# Negative_Rail.net
KiCad netlist of a schematic drawn in Altium Designer
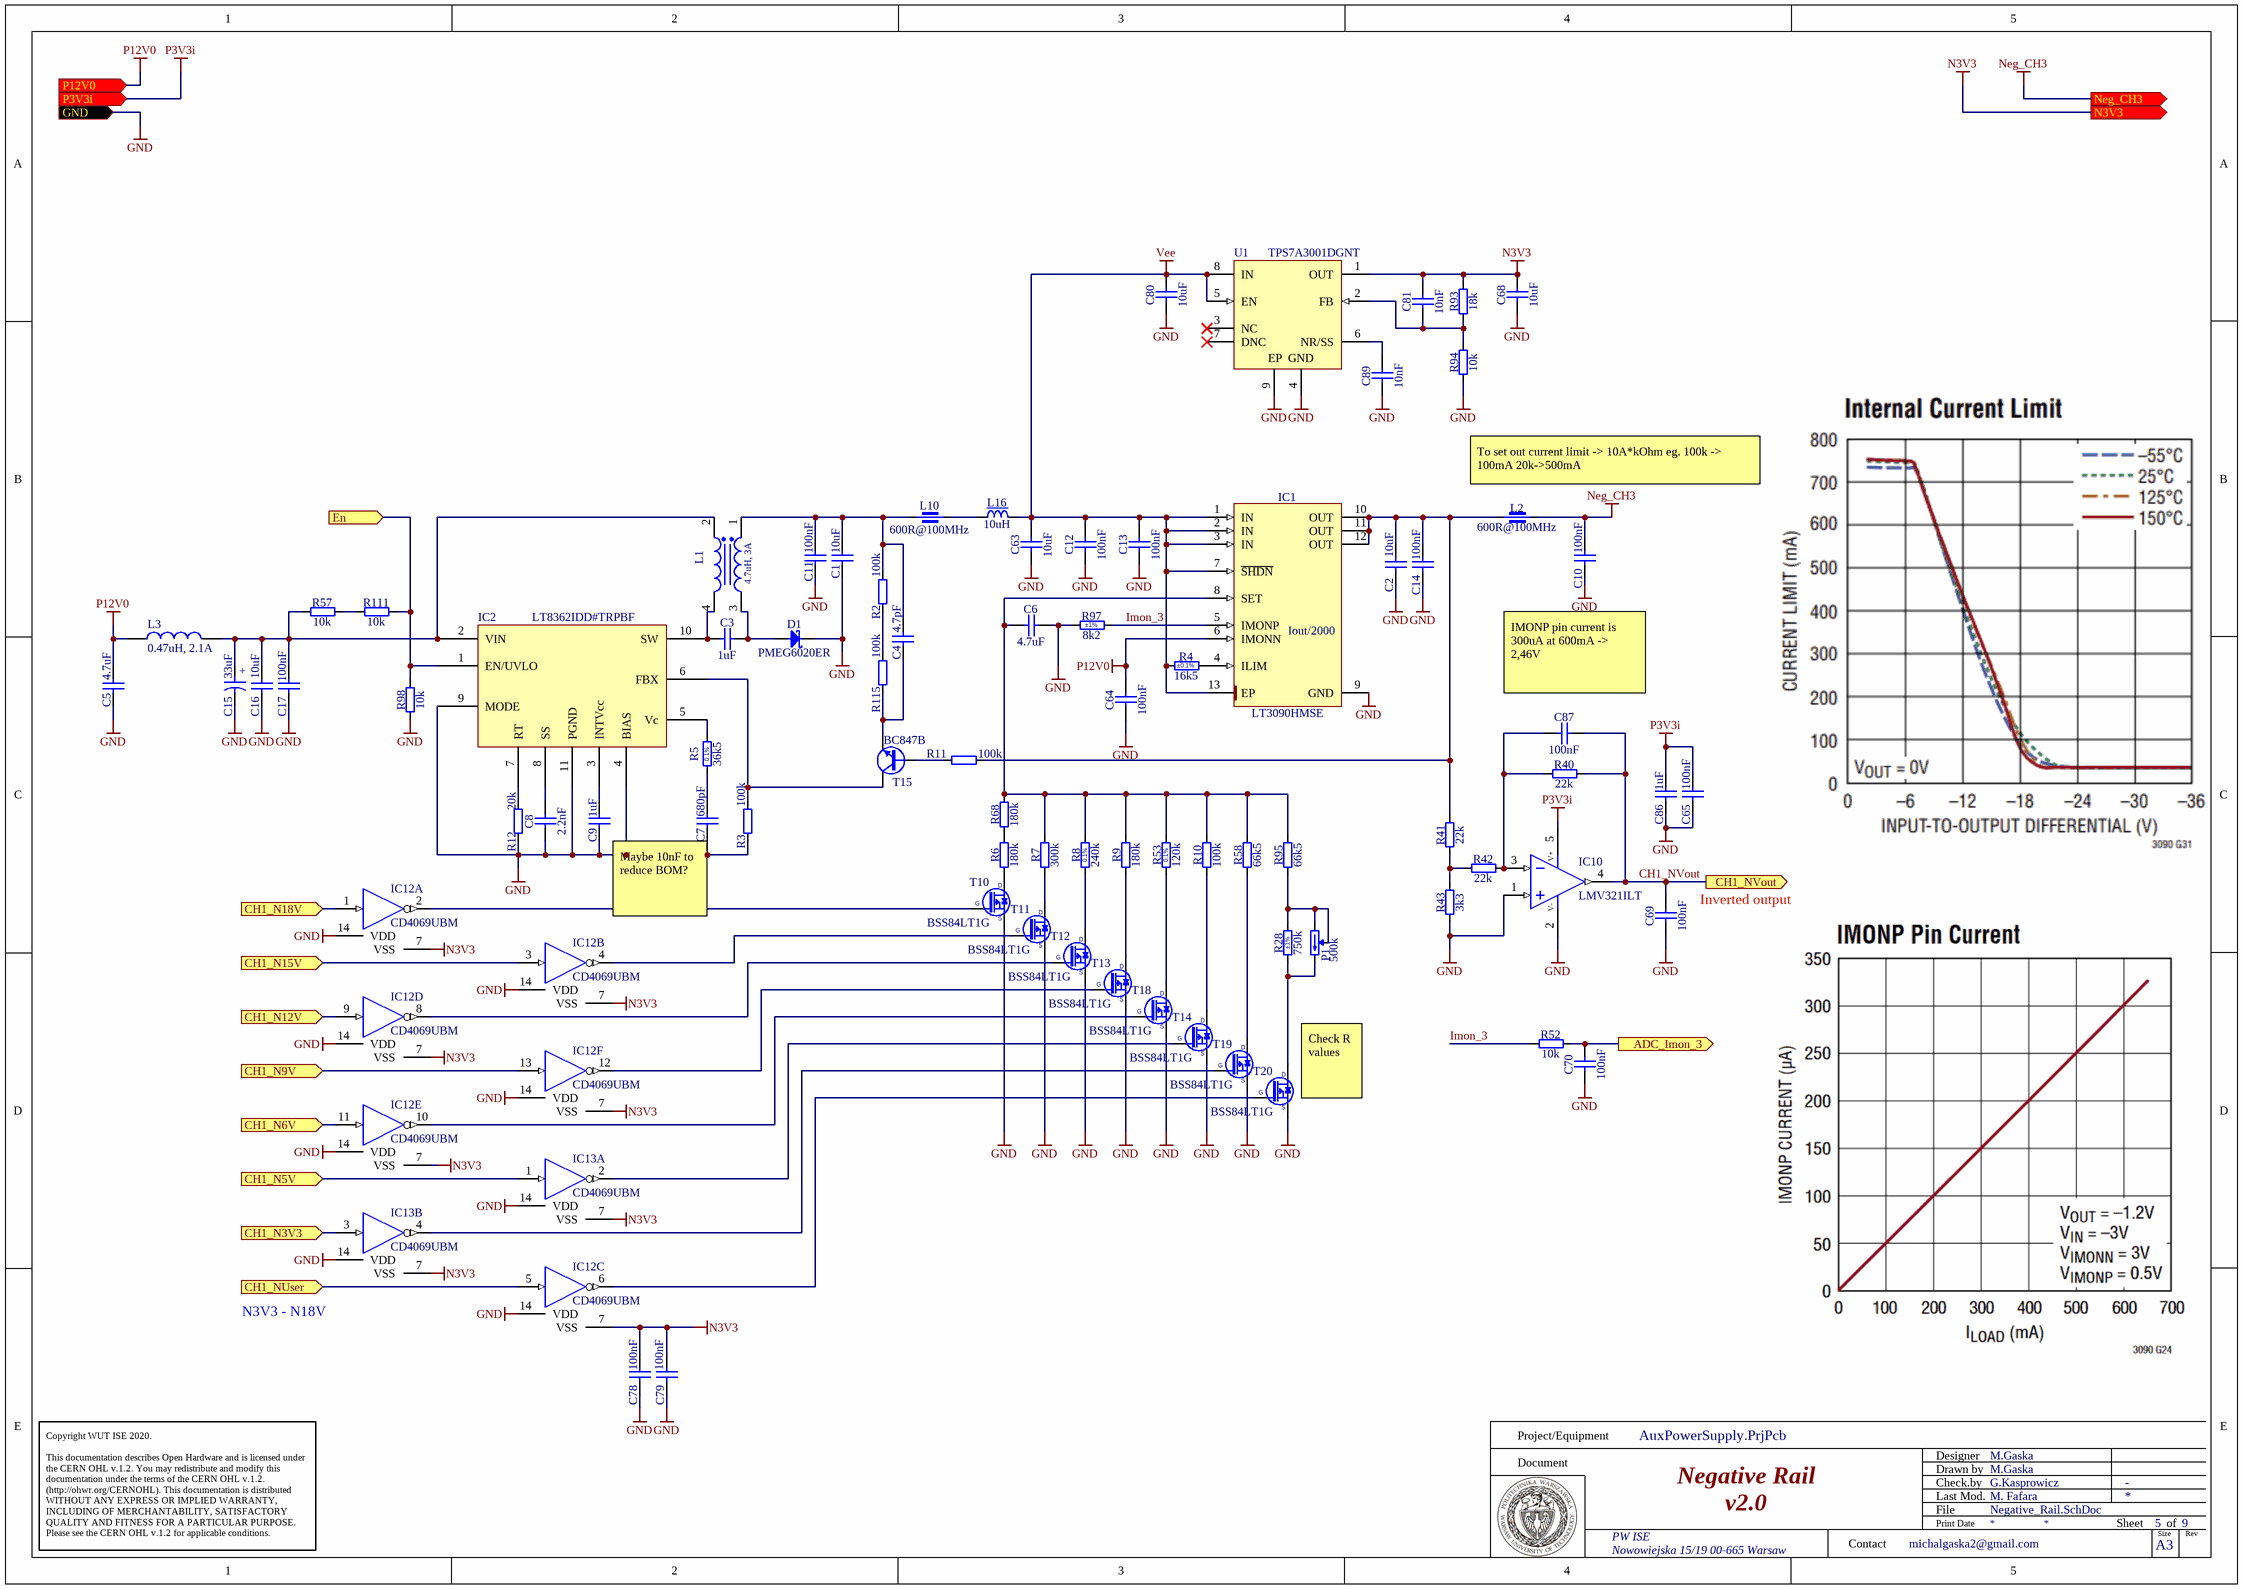
[diagram p0: Negative_Rail.SchDoc]

(export (version "E")
  (design (tool "Eeschema 10.0.6"))
  (components
    (comp (ref "C1")
      (value "10uF")
      (footprint "CAPC3216X190N")
      (description "Non-polarised capacitor")
      (fields
        (field (name "PART NUMBER") "CC1206_10UF_35V_10%_X7R_YUDEN_GMJ316BB7106KLHT")
        (field (name "VOLTAGE") "35V")
        (field (name "AUTHOR") "CERN DEM BC")
      )
      (libsource (lib "Capacitors") (part "Capacitor - non polarized"))
    )
    (comp (ref "C2")
      (value "10uF")
      (footprint "CAPC3216X190N")
      (description "Non-polarised capacitor")
      (fields
        (field (name "PART NUMBER") "CC1206_10UF_35V_10%_X7R_YUDEN_GMJ316BB7106KLHT")
        (field (name "VOLTAGE") "35V")
        (field (name "AUTHOR") "CERN DEM BC")
      )
      (libsource (lib "Capacitors") (part "Capacitor - non polarized"))
    )
    (comp (ref "C3")
      (value "1uF")
      (footprint "CAPC3216X140N")
      (description "Non-polarised capacitor")
      (fields
        (field (name "PART NUMBER") "CC1206_1UF_100V_10%_X7R")
        (field (name "VOLTAGE") "100V")
        (field (name "AUTHOR") "CERN DEM BC")
      )
      (libsource (lib "Capacitors") (part "Capacitor - non polarized"))
    )
    (comp (ref "C4")
      (value "4.7pF")
      (footprint "CAPC1608X87N")
      (description "Non-polarised capacitor")
      (fields
        (field (name "PART NUMBER") "CC0603_4.7PF_50V_0.25PF_NP0")
        (field (name "VOLTAGE") "50V")
        (field (name "AUTHOR") "CERN DEM JLC")
      )
      (libsource (lib "Capacitors") (part "Capacitor - non polarized"))
    )
    (comp (ref "C5")
      (value "4.7uF")
      (footprint "CAPC1608X90N")
      (description "Non-polarised capacitor")
      (fields
        (field (name "PART NUMBER") "CC0603_4.7UF_25V_10%_X5R")
        (field (name "VOLTAGE") "25V")
        (field (name "AUTHOR") "CERN DEM JLC")
      )
      (libsource (lib "Capacitors") (part "Capacitor - non polarized"))
    )
    (comp (ref "C6")
      (value "4.7uF")
      (footprint "CAPC1608X90N")
      (description "Non-polarised capacitor")
      (fields
        (field (name "PART NUMBER") "CC0603_4.7UF_25V_10%_X5R")
        (field (name "VOLTAGE") "25V")
        (field (name "AUTHOR") "CERN DEM JLC")
      )
      (libsource (lib "Capacitors") (part "Capacitor - non polarized"))
    )
    (comp (ref "C7")
      (value "680pF")
      (footprint "CAPC1608X87N")
      (description "Non-polarised capacitor")
      (fields
        (field (name "PART NUMBER") "CC0603_680PF_50V_5%_NP0")
        (field (name "VOLTAGE") "50V")
        (field (name "AUTHOR") "CERN DEM JLC")
      )
      (libsource (lib "Capacitors") (part "Capacitor - non polarized"))
    )
    (comp (ref "C8")
      (value "2.2nF")
      (footprint "CAPC1005X55N")
      (description "Non-polarised capacitor")
      (fields
        (field (name "PART NUMBER") "CC0402_2.2NF_50V_10%_X7R")
        (field (name "VOLTAGE") "50V")
        (field (name "AUTHOR") "CERN DEM JLC")
      )
      (libsource (lib "Capacitors") (part "Capacitor - non polarized"))
    )
    (comp (ref "C9")
      (value "1uF")
      (footprint "CAPC1608X87N")
      (description "Non-polarised capacitor")
      (fields
        (field (name "PART NUMBER") "CC0603_1UF_16V_10%_X7R")
        (field (name "VOLTAGE") "16V")
        (field (name "AUTHOR") "CERN DEM JLC")
      )
      (libsource (lib "Capacitors") (part "Capacitor - non polarized"))
    )
    (comp (ref "C10")
      (value "100nF")
      (footprint "CAPC1608X87N")
      (description "Non-polarised capacitor")
      (fields
        (field (name "PART NUMBER") "CC0603_100NF_50V_10%_X5R")
        (field (name "VOLTAGE") "50V")
        (field (name "AUTHOR") "CERN DEM MR")
      )
      (libsource (lib "Capacitors") (part "Capacitor - non polarized"))
    )
    (comp (ref "C11")
      (value "100nF")
      (footprint "CAPC1608X87N")
      (description "Non-polarised capacitor")
      (fields
        (field (name "PART NUMBER") "CC0603_100NF_50V_10%_X5R")
        (field (name "VOLTAGE") "50V")
        (field (name "AUTHOR") "CERN DEM MR")
      )
      (libsource (lib "Capacitors") (part "Capacitor - non polarized"))
    )
    (comp (ref "C12")
      (value "100nF")
      (footprint "CAPC1608X87N")
      (description "Non-polarised capacitor")
      (fields
        (field (name "PART NUMBER") "CC0603_100NF_50V_10%_X5R")
        (field (name "VOLTAGE") "50V")
        (field (name "AUTHOR") "CERN DEM MR")
      )
      (libsource (lib "Capacitors") (part "Capacitor - non polarized"))
    )
    (comp (ref "C13")
      (value "100nF")
      (footprint "CAPC1608X87N")
      (description "Non-polarised capacitor")
      (fields
        (field (name "PART NUMBER") "CC0603_100NF_50V_10%_X5R")
        (field (name "VOLTAGE") "50V")
        (field (name "AUTHOR") "CERN DEM MR")
      )
      (libsource (lib "Capacitors") (part "Capacitor - non polarized"))
    )
    (comp (ref "C14")
      (value "100nF")
      (footprint "CAPC1608X87N")
      (description "Non-polarised capacitor")
      (fields
        (field (name "PART NUMBER") "CC0603_100NF_50V_10%_X5R")
        (field (name "VOLTAGE") "50V")
        (field (name "AUTHOR") "CERN DEM MR")
      )
      (libsource (lib "Capacitors") (part "Capacitor - non polarized"))
    )
    (comp (ref "C15")
      (value "33uF")
      (footprint "CAPAE660X540N")
      (description "Polarised capacitor")
      (fields
        (field (name "PART NUMBER") "CAE660-540_33UF_35V_20%")
        (field (name "VOLTAGE") "35V")
        (field (name "AUTHOR") "CERN DEM JLC")
      )
      (libsource (lib "Capacitors") (part "Capacitor - polarized"))
    )
    (comp (ref "C16")
      (value "10uF")
      (footprint "CAPC3216X190N")
      (description "Non-polarised capacitor")
      (fields
        (field (name "PART NUMBER") "CC1206_10UF_35V_10%_X7R_YUDEN_GMJ316BB7106KLHT")
        (field (name "VOLTAGE") "35V")
        (field (name "AUTHOR") "CERN DEM BC")
      )
      (libsource (lib "Capacitors") (part "Capacitor - non polarized"))
    )
    (comp (ref "C17")
      (value "100nF")
      (footprint "CAPC1608X87N")
      (description "Non-polarised capacitor")
      (fields
        (field (name "PART NUMBER") "CC0603_100NF_50V_10%_X5R")
        (field (name "VOLTAGE") "50V")
        (field (name "AUTHOR") "CERN DEM MR")
      )
      (libsource (lib "Capacitors") (part "Capacitor - non polarized"))
    )
    (comp (ref "C63")
      (value "10uF")
      (footprint "CAPC3216X190N")
      (description "Non-polarised capacitor")
      (fields
        (field (name "PART NUMBER") "CC1206_10UF_35V_10%_X7R_YUDEN_GMJ316BB7106KLHT")
        (field (name "VOLTAGE") "35V")
        (field (name "AUTHOR") "CERN DEM BC")
      )
      (libsource (lib "Capacitors") (part "Capacitor - non polarized"))
    )
    (comp (ref "C64")
      (value "100nF")
      (footprint "CAPC1608X87N")
      (description "Non-polarised capacitor")
      (fields
        (field (name "PART NUMBER") "CC0603_100NF_50V_10%_X5R")
        (field (name "VOLTAGE") "50V")
        (field (name "AUTHOR") "CERN DEM MR")
      )
      (libsource (lib "Capacitors") (part "Capacitor - non polarized"))
    )
    (comp (ref "C65")
      (value "100nF")
      (footprint "CAPC1608X87N")
      (description "Non-polarised capacitor")
      (fields
        (field (name "PART NUMBER") "CC0603_100NF_50V_10%_X5R")
        (field (name "VOLTAGE") "50V")
        (field (name "AUTHOR") "CERN DEM MR")
      )
      (libsource (lib "Capacitors") (part "Capacitor - non polarized"))
    )
    (comp (ref "C68")
      (value "10uF")
      (footprint "CAPC3216X190N")
      (description "Non-polarised capacitor")
      (fields
        (field (name "PART NUMBER") "CC1206_10UF_35V_10%_X7R_YUDEN_GMJ316BB7106KLHT")
        (field (name "VOLTAGE") "35V")
        (field (name "AUTHOR") "CERN DEM BC")
      )
      (libsource (lib "Capacitors") (part "Capacitor - non polarized"))
    )
    (comp (ref "C69")
      (value "100nF")
      (footprint "CAPC1608X87N")
      (description "Non-polarised capacitor")
      (fields
        (field (name "PART NUMBER") "CC0603_100NF_50V_10%_X5R")
        (field (name "VOLTAGE") "50V")
        (field (name "AUTHOR") "CERN DEM MR")
      )
      (libsource (lib "Capacitors") (part "Capacitor - non polarized"))
    )
    (comp (ref "C70")
      (value "100nF")
      (footprint "CAPC1608X87N")
      (description "Non-polarised capacitor")
      (fields
        (field (name "PART NUMBER") "CC0603_100NF_50V_10%_X5R")
        (field (name "VOLTAGE") "50V")
        (field (name "AUTHOR") "CERN DEM MR")
      )
      (libsource (lib "Capacitors") (part "Capacitor - non polarized"))
    )
    (comp (ref "C78")
      (value "100nF")
      (footprint "CAPC1608X87N")
      (description "Non-polarised capacitor")
      (fields
        (field (name "PART NUMBER") "CC0603_100NF_50V_10%_X7R")
        (field (name "VOLTAGE") "50V")
        (field (name "AUTHOR") "CERN DEM JLC")
      )
      (libsource (lib "Capacitors") (part "Capacitor - non polarized"))
    )
    (comp (ref "C79")
      (value "100nF")
      (footprint "CAPC1608X87N")
      (description "Non-polarised capacitor")
      (fields
        (field (name "PART NUMBER") "CC0603_100NF_50V_10%_X7R")
        (field (name "VOLTAGE") "50V")
        (field (name "AUTHOR") "CERN DEM JLC")
      )
      (libsource (lib "Capacitors") (part "Capacitor - non polarized"))
    )
    (comp (ref "C80")
      (value "10uF")
      (footprint "CAPC3216X190N")
      (description "Non-polarised capacitor")
      (fields
        (field (name "PART NUMBER") "CC1206_10UF_35V_10%_X7R_YUDEN_GMJ316BB7106KLHT")
        (field (name "VOLTAGE") "35V")
        (field (name "AUTHOR") "CERN DEM BC")
      )
      (libsource (lib "Capacitors") (part "Capacitor - non polarized"))
    )
    (comp (ref "C81")
      (value "10nF")
      (footprint "CAPC1608X87N")
      (description "Non-polarised capacitor")
      (fields
        (field (name "PART NUMBER") "CC0603_10NF_50V_10%_X7R")
        (field (name "VOLTAGE") "50V")
        (field (name "AUTHOR") "CERN DEM JLC")
      )
      (libsource (lib "Capacitors") (part "Capacitor - non polarized"))
    )
    (comp (ref "C86")
      (value "1uF")
      (footprint "CAPC1608X87N")
      (description "Non-polarised capacitor")
      (fields
        (field (name "PART NUMBER") "CC0603_1UF_16V_10%_X7R")
        (field (name "VOLTAGE") "16V")
        (field (name "AUTHOR") "CERN DEM JLC")
      )
      (libsource (lib "Capacitors") (part "Capacitor - non polarized"))
    )
    (comp (ref "C87")
      (value "100nF")
      (footprint "CAPC1608X87N")
      (description "Non-polarised capacitor")
      (fields
        (field (name "PART NUMBER") "CC0603_100NF_50V_10%_X5R")
        (field (name "VOLTAGE") "50V")
        (field (name "AUTHOR") "CERN DEM MR")
      )
      (libsource (lib "Capacitors") (part "Capacitor - non polarized"))
    )
    (comp (ref "C89")
      (value "10nF")
      (footprint "CAPC1608X87N")
      (description "Non-polarised capacitor")
      (fields
        (field (name "PART NUMBER") "CC0603_10NF_50V_10%_X7R")
        (field (name "VOLTAGE") "50V")
        (field (name "AUTHOR") "CERN DEM JLC")
      )
      (libsource (lib "Capacitors") (part "Capacitor - non polarized"))
    )
    (comp (ref "D1")
      (value "PMEG6020ER")
      (footprint "SODFL3517X110N")
      (description "Schottky Diode")
      (fields
        (field (name "VOLTAGE") "60V")
        (field (name "POWER") "2A")
        (field (name "AUTHOR") "CERN DEM JMW")
      )
      (libsource (lib "ICs And Semiconductors") (part "Diode Schottky"))
    )
    (comp (ref "IC1")
      (value "LT3090HMSE")
      (footprint "SOP65P490X110-13N-R175X294")
      (description "–36V, 600mA Negative Linear Regulator with Programmable Current Limit")
      (fields
        (field (name "PART NUMBER") "LT3090HMSE#PBF")
        (field (name "MANUFACTURER") "LINEAR TECHNOLOGY")
        (field (name "AUTHOR") "CERN DEM JLC")
      )
      (libsource (lib "ICs And Semiconductors") (part "LT3090HMSE#PBF"))
    )
    (comp (ref "IC2")
      (value "LT8362IDD#TRPBF")
      (footprint "SON50P300X300X80-11N-R160X240")
      (libsource (lib "MG_lib") (part "LT8362IDD#TRPBF"))
    )
    (comp (ref "IC10")
      (value "LMV321ILT")
      (footprint "SOT95P280X145-5N")
      (description "Operational Amplifier")
      (fields (field (name "MANUFACTURER") "ST MICROELECTRONICS") (field (name "AUTHOR") "CERN DEM MR"))
      (libsource (lib "ICs And Semiconductors") (part "Operational Amplifier Type10"))
    )
    (comp (ref "IC12")
      (value "CD4069UBM")
      (footprint "SOIC127P600X175-14N")
      (description "Hex Inverter")
      (fields (field (name "MANUFACTURER") "TEXAS INSTRUMENTS") (field (name "AUTHOR") "CERN DEM JMW"))
      (libsource (lib "ICs And Semiconductors") (part "4069"))
    )
    (comp (ref "IC13")
      (value "CD4069UBM")
      (footprint "SOIC127P600X175-14N")
      (description "Hex Inverter")
      (fields (field (name "MANUFACTURER") "TEXAS INSTRUMENTS") (field (name "AUTHOR") "CERN DEM JMW"))
      (libsource (lib "ICs And Semiconductors") (part "4069"))
    )
    (comp (ref "L1")
      (value "4.7uH, 3A")
      (footprint "WE-DD_1260")
      (description "WE-DD SMT Shielded Coupled Inductor, size 1260, 4.7uH, 3A")
      (fields
        (field (name "MANUFACTURER") "Wurth Elektronik")
        (field (name "MANUFACTURER PART NUMBER") "744871004")
      )
      (libsource (lib "744871470_Altium_WE-DD_rev20a") (part "744871004"))
    )
    (comp (ref "L2")
      (value "600R@100MHz")
      (footprint "INDC2012X110N")
      (fields
        (field (name "PART NUMBER") "IND0805_WURTH_742792040")
        (field (name "POWER") "2A")
        (field (name "TOLERANCE") "±25%")
        (field (name "AUTHOR") "CERN DEM JLC")
      )
      (libsource (lib "Inductors & Transformers") (part "Ferrite Bead"))
    )
    (comp (ref "L3")
      (value "0.47uH, 2.1A")
      (footprint "WE-PMI_0806_H1")
      (description "WE-PMI Power Multilayer Inductor, size 0806, 0.47uH, 2.1A")
      (fields
        (field (name "MANUFACTURER") "Wurth Elektronik")
        (field (name "MANUFACTURER PART NUMBER") "74479876147")
      )
      (libsource (lib "Altium_WE-PMI_rev20a") (part "74479876147"))
    )
    (comp (ref "L10")
      (value "600R@100MHz")
      (footprint "INDC2012X110N")
      (fields
        (field (name "PART NUMBER") "IND0805_WURTH_742792040")
        (field (name "POWER") "2A")
        (field (name "TOLERANCE") "±25%")
        (field (name "AUTHOR") "CERN DEM JLC")
      )
      (libsource (lib "Inductors & Transformers") (part "Ferrite Bead"))
    )
    (comp (ref "L16")
      (value "10uH")
      (footprint "IND_BOURNS_PM43")
      (description "Inductor With Core")
      (fields
        (field (name "PART NUMBER") "IND_10UH_20%_BOURNS_PM43")
        (field (name "POWER") "1.15A")
        (field (name "AUTHOR") "CERN DEM JLC")
      )
      (libsource (lib "Inductors & Transformers") (part "Inductor With Magnetic core"))
    )
    (comp (ref "P1")
      (value "500k")
      (footprint "Bourns_3059Y")
      (description "Trimmer, Cermet, 1W, 500000ohm, 400V, 10% +/-Tol, 100ppm/Cel, 22 Turn(s)")
      (fields (field (name "POWER") "1W") (field (name "TOLERANCE") "10%"))
      (libsource (lib "TechnoSystem Workspace") (part "Trimming Potentiometer"))
    )
    (comp (ref "R2")
      (value "100k")
      (footprint "RESC1608X55N")
      (description "Resistor - 1%")
      (fields
        (field (name "PART NUMBER") "R0603_100K_1%_0.1W_100PPM")
        (field (name "POWER") "0.1W")
        (field (name "AUTHOR") "CERN DEM JLC")
      )
      (libsource (lib "Resistors") (part "Resistor - 1%"))
    )
    (comp (ref "R3")
      (value "100k")
      (footprint "RESC1608X55N")
      (description "Resistor - 1%")
      (fields
        (field (name "PART NUMBER") "R0603_100K_1%_0.1W_100PPM")
        (field (name "POWER") "0.1W")
        (field (name "AUTHOR") "CERN DEM JLC")
      )
      (libsource (lib "Resistors") (part "Resistor - 1%"))
    )
    (comp (ref "R4")
      (value "16k5")
      (footprint "RESC1608X55N")
      (description "Resistor - 0.1%")
      (fields
        (field (name "TOLERANCE") "±0.1%")
        (field (name "PART NUMBER") "R0603_16K5_0.1%_0.063W_10PPM")
        (field (name "POWER") "0.063W")
        (field (name "AUTHOR") "CERN DEM JLC")
      )
      (libsource (lib "") (part "Resistor - 0.1%_1"))
    )
    (comp (ref "R5")
      (value "36k5")
      (footprint "RESC1608X55N")
      (description "Resistor - 0.1%")
      (fields
        (field (name "PART NUMBER") "R0603_36K5_0.1%_0.063W_10PPM")
        (field (name "POWER") "0.063W")
        (field (name "AUTHOR") "CERN DEM JLC")
      )
      (libsource (lib "Resistors") (part "Resistor - 0.1%"))
    )
    (comp (ref "R6")
      (value "180k")
      (footprint "RESC2012X60N")
      (description "Resistor - 1%")
      (fields
        (field (name "PART NUMBER") "R0805_180K_1%_0.125W_100PPM")
        (field (name "POWER") "0.125W")
        (field (name "AUTHOR") "CERN DEM JLC")
      )
      (libsource (lib "Resistors") (part "Resistor - 1%"))
    )
    (comp (ref "R7")
      (value "300k")
      (footprint "RESC2012X60N")
      (description "Resistor - 1%")
      (fields
        (field (name "PART NUMBER") "R0805_300K_1%_0.125W_100PPM")
        (field (name "POWER") "0.125W")
        (field (name "AUTHOR") "CERN DEM JLC")
      )
      (libsource (lib "Resistors") (part "Resistor - 1%"))
    )
    (comp (ref "R8")
      (value "240k")
      (footprint "RESC2012X60N")
      (description "Resistor - 0.1%")
      (fields
        (field (name "PART NUMBER") "R0805_240K_0.1%_0.1W_10PPM")
        (field (name "POWER") "0.1W")
        (field (name "AUTHOR") "CERN DEM JLC")
      )
      (libsource (lib "Resistors") (part "Resistor - 0.1%"))
    )
    (comp (ref "R9")
      (value "180k")
      (footprint "RESC2012X60N")
      (description "Resistor - 1%")
      (fields
        (field (name "PART NUMBER") "R0805_180K_1%_0.125W_100PPM")
        (field (name "POWER") "0.125W")
        (field (name "AUTHOR") "CERN DEM JLC")
      )
      (libsource (lib "Resistors") (part "Resistor - 1%"))
    )
    (comp (ref "R10")
      (value "100k")
      (footprint "RESC2012X60N")
      (description "Resistor - 0.1%")
      (fields
        (field (name "PART NUMBER") "R0805_100K_0.1%_0.1W_10PPM")
        (field (name "POWER") "0.1W")
        (field (name "AUTHOR") "CERN DEM JLC")
      )
      (libsource (lib "Resistors") (part "Resistor - 0.1%"))
    )
    (comp (ref "R11")
      (value "100k")
      (footprint "RESC1608X55N")
      (description "Resistor - 1%")
      (fields
        (field (name "PART NUMBER") "R0603_100K_1%_0.1W_100PPM")
        (field (name "POWER") "0.1W")
        (field (name "AUTHOR") "CERN DEM JLC")
      )
      (libsource (lib "Resistors") (part "Resistor - 1%"))
    )
    (comp (ref "R12")
      (value "20k")
      (footprint "RESC1608X55N")
      (description "Resistor - 1%")
      (fields
        (field (name "PART NUMBER") "R0603_20K_1%_0.1W_100PPM")
        (field (name "POWER") "0.1W")
        (field (name "AUTHOR") "CERN DEM JLC")
      )
      (libsource (lib "Resistors") (part "Resistor - 1%"))
    )
    (comp (ref "R28")
      (value "750k")
      (footprint "RESC2012X60N")
      (description "Resistor - 1%")
      (fields
        (field (name "TOLERANCE") "±1%")
        (field (name "PART NUMBER") "R0805_750K_1%_0.125W_100PPM")
        (field (name "POWER") "0.125W")
        (field (name "AUTHOR") "CERN DEM JLC")
      )
      (libsource (lib "Resistors") (part "Resistor - 1%"))
    )
    (comp (ref "R40")
      (value "22k")
      (footprint "RESC1608X55N")
      (description "Resistor - 1%")
      (fields
        (field (name "PART NUMBER") "R0603_22K_1%_0.1W_100PPM")
        (field (name "POWER") "0.1W")
        (field (name "AUTHOR") "CERN DEM JLC")
      )
      (libsource (lib "Resistors") (part "Resistor - 1%"))
    )
    (comp (ref "R41")
      (value "22k")
      (footprint "RESC1608X55N")
      (description "Resistor - 1%")
      (fields
        (field (name "PART NUMBER") "R0603_22K_1%_0.1W_100PPM")
        (field (name "POWER") "0.1W")
        (field (name "AUTHOR") "CERN DEM JLC")
      )
      (libsource (lib "Resistors") (part "Resistor - 1%"))
    )
    (comp (ref "R42")
      (value "22k")
      (footprint "RESC1608X55N")
      (description "Resistor - 1%")
      (fields
        (field (name "PART NUMBER") "R0603_22K_1%_0.1W_100PPM")
        (field (name "POWER") "0.1W")
        (field (name "AUTHOR") "CERN DEM JLC")
      )
      (libsource (lib "Resistors") (part "Resistor - 1%"))
    )
    (comp (ref "R43")
      (value "3k3")
      (footprint "RESC1608X55N")
      (description "Resistor - 1%")
      (fields
        (field (name "PART NUMBER") "R0603_3K3_1%_0.1W_100PPM")
        (field (name "POWER") "0.1W")
        (field (name "AUTHOR") "CERN DEM JLC")
      )
      (libsource (lib "Resistors") (part "Resistor - 1%"))
    )
    (comp (ref "R52")
      (value "10k")
      (footprint "RESC1608X55N")
      (description "Resistor - 1%")
      (fields
        (field (name "PART NUMBER") "R0603_10K_1%_0.1W_100PPM")
        (field (name "POWER") "0.1W")
        (field (name "AUTHOR") "CERN DEM JLC")
      )
      (libsource (lib "Resistors") (part "Resistor - 1%"))
    )
    (comp (ref "R53")
      (value "120k")
      (footprint "RESC2012X60N")
      (description "Resistor - 0.1%")
      (fields
        (field (name "PART NUMBER") "R0805_120K_0.1%_0.125W_25PPM")
        (field (name "POWER") "0.125W")
        (field (name "AUTHOR") "CERN DEM JLC")
      )
      (libsource (lib "Resistors") (part "Resistor - 0.1%"))
    )
    (comp (ref "R57")
      (value "10k")
      (footprint "RESC1608X55N")
      (description "Resistor - 1%")
      (fields
        (field (name "PART NUMBER") "R0603_10K_1%_0.1W_100PPM")
        (field (name "POWER") "0.1W")
        (field (name "AUTHOR") "CERN DEM JLC")
      )
      (libsource (lib "Resistors") (part "Resistor - 1%"))
    )
    (comp (ref "R58")
      (value "66k5")
      (footprint "RESC2012X60N")
      (description "Resistor - 0.1%")
      (fields
        (field (name "PART NUMBER") "R0805_66K5_0.1%_0.1W_10PPM")
        (field (name "POWER") "0.1W")
        (field (name "AUTHOR") "CERN DEM JLC")
      )
      (libsource (lib "Resistors") (part "Resistor - 0.1%"))
    )
    (comp (ref "R68")
      (value "180k")
      (footprint "RESC2012X60N")
      (description "Resistor - 1%")
      (fields
        (field (name "PART NUMBER") "R0805_180K_1%_0.125W_100PPM")
        (field (name "POWER") "0.125W")
        (field (name "AUTHOR") "CERN DEM JLC")
      )
      (libsource (lib "Resistors") (part "Resistor - 1%"))
    )
    (comp (ref "R93")
      (value "18k")
      (footprint "RESC1608X55N")
      (description "Resistor - 1%")
      (fields
        (field (name "PART NUMBER") "R0603_18K_1%_0.1W_100PPM")
        (field (name "POWER") "0.1W")
        (field (name "AUTHOR") "CERN DEM JLC")
      )
      (libsource (lib "Resistors") (part "Resistor - 1%"))
    )
    (comp (ref "R94")
      (value "10k")
      (footprint "RESC1608X55N")
      (description "Resistor - 1%")
      (fields
        (field (name "PART NUMBER") "R0603_10K_1%_0.1W_100PPM")
        (field (name "POWER") "0.1W")
        (field (name "AUTHOR") "CERN DEM JLC")
      )
      (libsource (lib "Resistors") (part "Resistor - 1%"))
    )
    (comp (ref "R95")
      (value "66k5")
      (footprint "RESC2012X60N")
      (description "Resistor - 0.1%")
      (fields
        (field (name "PART NUMBER") "R0805_66K5_0.1%_0.1W_10PPM")
        (field (name "POWER") "0.1W")
        (field (name "AUTHOR") "CERN DEM JLC")
      )
      (libsource (lib "Resistors") (part "Resistor - 0.1%"))
    )
    (comp (ref "R97")
      (value "8k2")
      (footprint "RESC1608X55N")
      (description "Resistor - 1%")
      (fields
        (field (name "TOLERANCE") "±1%")
        (field (name "PART NUMBER") "R0603_8K2_1%_0.1W_100PPM")
        (field (name "POWER") "0.1W")
        (field (name "AUTHOR") "CERN DEM JLC")
      )
      (libsource (lib "Resistors") (part "Resistor - 1%"))
    )
    (comp (ref "R98")
      (value "10k")
      (footprint "RESC1608X55N")
      (description "Resistor - 1%")
      (fields
        (field (name "PART NUMBER") "R0603_10K_1%_0.1W_100PPM")
        (field (name "POWER") "0.1W")
        (field (name "AUTHOR") "CERN DEM JLC")
      )
      (libsource (lib "Resistors") (part "Resistor - 1%"))
    )
    (comp (ref "R111")
      (value "10k")
      (footprint "RESC1608X55N")
      (description "Resistor - 1%")
      (fields
        (field (name "PART NUMBER") "R0603_10K_1%_0.1W_100PPM")
        (field (name "POWER") "0.1W")
        (field (name "AUTHOR") "CERN DEM JLC")
      )
      (libsource (lib "Resistors") (part "Resistor - 1%"))
    )
    (comp (ref "R115")
      (value "100k")
      (footprint "RESC1608X55N")
      (description "Resistor - 1%")
      (fields
        (field (name "PART NUMBER") "R0603_100K_1%_0.1W_100PPM")
        (field (name "POWER") "0.1W")
        (field (name "AUTHOR") "CERN DEM JLC")
      )
      (libsource (lib "Resistors") (part "Resistor - 1%"))
    )
    (comp (ref "T10")
      (value "BSS84LT1G")
      (footprint "SOT95P240X110-3N")
      (description "P-CHANNEL MOSFET WITH DIODE")
      (fields
        (field (name "MANUFACTURER") "ON SEMICONDUCTOR")
        (field (name "MANUFACTURER PART NUMBER") "BSS84L")
        (field (name "AUTHOR") "CERN DEM JLC")
      )
      (libsource (lib "ICs And Semiconductors") (part "P-MOSFET-D 1G 2S 3D"))
    )
    (comp (ref "T11")
      (value "BSS84LT1G")
      (footprint "SOT95P240X110-3N")
      (description "P-CHANNEL MOSFET WITH DIODE")
      (fields
        (field (name "MANUFACTURER") "ON SEMICONDUCTOR")
        (field (name "MANUFACTURER PART NUMBER") "BSS84L")
        (field (name "AUTHOR") "CERN DEM JLC")
      )
      (libsource (lib "ICs And Semiconductors") (part "P-MOSFET-D 1G 2S 3D"))
    )
    (comp (ref "T12")
      (value "BSS84LT1G")
      (footprint "SOT95P240X110-3N")
      (description "P-CHANNEL MOSFET WITH DIODE")
      (fields
        (field (name "MANUFACTURER") "ON SEMICONDUCTOR")
        (field (name "MANUFACTURER PART NUMBER") "BSS84L")
        (field (name "AUTHOR") "CERN DEM JLC")
      )
      (libsource (lib "ICs And Semiconductors") (part "P-MOSFET-D 1G 2S 3D"))
    )
    (comp (ref "T13")
      (value "BSS84LT1G")
      (footprint "SOT95P240X110-3N")
      (description "P-CHANNEL MOSFET WITH DIODE")
      (fields
        (field (name "MANUFACTURER") "ON SEMICONDUCTOR")
        (field (name "MANUFACTURER PART NUMBER") "BSS84L")
        (field (name "AUTHOR") "CERN DEM JLC")
      )
      (libsource (lib "ICs And Semiconductors") (part "P-MOSFET-D 1G 2S 3D"))
    )
    (comp (ref "T14")
      (value "BSS84LT1G")
      (footprint "SOT95P240X110-3N")
      (description "P-CHANNEL MOSFET WITH DIODE")
      (fields
        (field (name "MANUFACTURER") "ON SEMICONDUCTOR")
        (field (name "MANUFACTURER PART NUMBER") "BSS84L")
        (field (name "AUTHOR") "CERN DEM JLC")
      )
      (libsource (lib "ICs And Semiconductors") (part "P-MOSFET-D 1G 2S 3D"))
    )
    (comp (ref "T15")
      (value "BC847B")
      (footprint "SOT95P230X110-3N")
      (description "NPN Transistor")
      (fields (field (name "MANUFACTURER") "NXP SEMICONDUCTORS") (field (name "AUTHOR") "CERN DEM JLC"))
      (libsource (lib "ICs And Semiconductors") (part "NPN B1 E2 C3"))
    )
    (comp (ref "T18")
      (value "BSS84LT1G")
      (footprint "SOT95P240X110-3N")
      (description "P-CHANNEL MOSFET WITH DIODE")
      (fields
        (field (name "MANUFACTURER") "ON SEMICONDUCTOR")
        (field (name "MANUFACTURER PART NUMBER") "BSS84L")
        (field (name "AUTHOR") "CERN DEM JLC")
      )
      (libsource (lib "ICs And Semiconductors") (part "P-MOSFET-D 1G 2S 3D"))
    )
    (comp (ref "T19")
      (value "BSS84LT1G")
      (footprint "SOT95P240X110-3N")
      (description "P-CHANNEL MOSFET WITH DIODE")
      (fields
        (field (name "MANUFACTURER") "ON SEMICONDUCTOR")
        (field (name "MANUFACTURER PART NUMBER") "BSS84L")
        (field (name "AUTHOR") "CERN DEM JLC")
      )
      (libsource (lib "ICs And Semiconductors") (part "P-MOSFET-D 1G 2S 3D"))
    )
    (comp (ref "T20")
      (value "BSS84LT1G")
      (footprint "SOT95P240X110-3N")
      (description "P-CHANNEL MOSFET WITH DIODE")
      (fields
        (field (name "MANUFACTURER") "ON SEMICONDUCTOR")
        (field (name "MANUFACTURER PART NUMBER") "BSS84L")
        (field (name "AUTHOR") "CERN DEM JLC")
      )
      (libsource (lib "ICs And Semiconductors") (part "P-MOSFET-D 1G 2S 3D"))
    )
    (comp (ref "U1")
      (value "TPS7A3001DGNT")
      (footprint "TI-DGN8-1760X1425TP_M")
      (fields (field (name "MANUFACTURER") "Texas Instruments"))
      (libsource (lib "Altium Content Vault") (part "TI-TPS7A3001DGN8-1760X1425TP"))
    )
  )
  (nets
    (net (code "1") (name "/ADC_Imon_3") (class "Default")
      (node (ref "C70") (pin "2") (pinfunction "2_2") (pintype "passive"))
      (node (ref "R52") (pin "2") (pinfunction "2_2") (pintype "passive"))
    )
    (net (code "2") (name "/CH1_N3V3") (class "Default")
      (node (ref "IC13") (pin "3") (pinfunction "IN_3") (pintype "input"))
    )
    (net (code "3") (name "/CH1_N5V") (class "Default")
      (node (ref "IC13") (pin "1") (pinfunction "IN_1") (pintype "input"))
    )
    (net (code "4") (name "/CH1_N6V") (class "Default")
      (node (ref "IC12") (pin "11") (pinfunction "IN_11") (pintype "input"))
    )
    (net (code "5") (name "/CH1_N9V") (class "Default")
      (node (ref "IC12") (pin "13") (pinfunction "IN_13") (pintype "input"))
    )
    (net (code "6") (name "/CH1_N12V") (class "Default")
      (node (ref "IC12") (pin "9") (pinfunction "IN_9") (pintype "input"))
    )
    (net (code "7") (name "/CH1_N15V") (class "Default")
      (node (ref "IC12") (pin "3") (pinfunction "IN_3") (pintype "input"))
    )
    (net (code "8") (name "/CH1_N18V") (class "Default")
      (node (ref "IC12") (pin "1") (pinfunction "IN_1") (pintype "input"))
    )
    (net (code "9") (name "/CH1_NUser") (class "Default")
      (node (ref "IC12") (pin "5") (pinfunction "IN_5") (pintype "input"))
    )
    (net (code "10") (name "/CH1_NVout") (class "Default")
      (node (ref "C69") (pin "2") (pinfunction "2_2") (pintype "passive"))
      (node (ref "C87") (pin "2") (pinfunction "2_2") (pintype "passive"))
      (node (ref "IC10") (pin "4") (pinfunction "OUT_4") (pintype "output"))
      (node (ref "R40") (pin "2") (pinfunction "2_2") (pintype "passive"))
    )
    (net (code "11") (name "/En") (class "Default")
      (node (ref "IC2") (pin "1") (pinfunction "EN/UVLO_1") (pintype "passive"))
      (node (ref "R111") (pin "2") (pinfunction "2_2") (pintype "passive"))
      (node (ref "R98") (pin "2") (pinfunction "2_2") (pintype "passive"))
    )
    (net (code "12") (name "/Imon_3") (class "Default")
      (node (ref "IC1") (pin "5") (pinfunction "IMONP_5") (pintype "input"))
      (node (ref "R52") (pin "1") (pinfunction "1_1") (pintype "passive"))
      (node (ref "R97") (pin "2") (pinfunction "2_2") (pintype "passive"))
    )
    (net (code "13") (name "GND") (class "Default")
      (node (ref "C1") (pin "1") (pinfunction "1_1") (pintype "passive"))
      (node (ref "C10") (pin "1") (pinfunction "1_1") (pintype "passive"))
      (node (ref "C11") (pin "1") (pinfunction "1_1") (pintype "passive"))
      (node (ref "C12") (pin "1") (pinfunction "1_1") (pintype "passive"))
      (node (ref "C13") (pin "1") (pinfunction "1_1") (pintype "passive"))
      (node (ref "C14") (pin "1") (pinfunction "1_1") (pintype "passive"))
      (node (ref "C15") (pin "2") (pinfunction "2_2") (pintype "passive"))
      (node (ref "C16") (pin "1") (pinfunction "1_1") (pintype "passive"))
      (node (ref "C17") (pin "1") (pinfunction "1_1") (pintype "passive"))
      (node (ref "C2") (pin "1") (pinfunction "1_1") (pintype "passive"))
      (node (ref "C5") (pin "1") (pinfunction "1_1") (pintype "passive"))
      (node (ref "C6") (pin "2") (pinfunction "2_2") (pintype "passive"))
      (node (ref "C63") (pin "1") (pinfunction "1_1") (pintype "passive"))
      (node (ref "C64") (pin "1") (pinfunction "1_1") (pintype "passive"))
      (node (ref "C65") (pin "1") (pinfunction "1_1") (pintype "passive"))
      (node (ref "C68") (pin "1") (pinfunction "1_1") (pintype "passive"))
      (node (ref "C69") (pin "1") (pinfunction "1_1") (pintype "passive"))
      (node (ref "C7") (pin "1") (pinfunction "1_1") (pintype "passive"))
      (node (ref "C70") (pin "1") (pinfunction "1_1") (pintype "passive"))
      (node (ref "C78") (pin "1") (pinfunction "1_1") (pintype "passive"))
      (node (ref "C79") (pin "1") (pinfunction "1_1") (pintype "passive"))
      (node (ref "C8") (pin "1") (pinfunction "1_1") (pintype "passive"))
      (node (ref "C80") (pin "1") (pinfunction "1_1") (pintype "passive"))
      (node (ref "C86") (pin "1") (pinfunction "1_1") (pintype "passive"))
      (node (ref "C89") (pin "1") (pinfunction "1_1") (pintype "passive"))
      (node (ref "C9") (pin "1") (pinfunction "1_1") (pintype "passive"))
      (node (ref "D1") (pin "1") (pinfunction "C_1") (pintype "passive"))
      (node (ref "IC1") (pin "9") (pinfunction "GND_9") (pintype "power_in"))
      (node (ref "IC10") (pin "1") (pinfunction "IN+_1") (pintype "input"))
      (node (ref "IC10") (pin "2") (pinfunction "V-_2") (pintype "power_in"))
      (node (ref "IC12") (pin "14") (pinfunction "VDD_14") (pintype "power_in"))
      (node (ref "IC13") (pin "14") (pinfunction "VDD_14") (pintype "power_in"))
      (node (ref "IC2") (pin "11") (pinfunction "PGND_11") (pintype "passive"))
      (node (ref "IC2") (pin "4") (pinfunction "BIAS_4") (pintype "passive"))
      (node (ref "IC2") (pin "9") (pinfunction "MODE_9") (pintype "passive"))
      (node (ref "R12") (pin "1") (pinfunction "1_1") (pintype "passive"))
      (node (ref "R3") (pin "1") (pinfunction "1_1") (pintype "passive"))
      (node (ref "R43") (pin "1") (pinfunction "1_1") (pintype "passive"))
      (node (ref "R94") (pin "1") (pinfunction "1_1") (pintype "passive"))
      (node (ref "R97") (pin "1") (pinfunction "1_1") (pintype "passive"))
      (node (ref "R98") (pin "1") (pinfunction "1_1") (pintype "passive"))
      (node (ref "T10") (pin "2") (pinfunction "S_2") (pintype "passive"))
      (node (ref "T11") (pin "2") (pinfunction "S_2") (pintype "passive"))
      (node (ref "T12") (pin "2") (pinfunction "S_2") (pintype "passive"))
      (node (ref "T13") (pin "2") (pinfunction "S_2") (pintype "passive"))
      (node (ref "T14") (pin "2") (pinfunction "S_2") (pintype "passive"))
      (node (ref "T18") (pin "2") (pinfunction "S_2") (pintype "passive"))
      (node (ref "T19") (pin "2") (pinfunction "S_2") (pintype "passive"))
      (node (ref "T20") (pin "2") (pinfunction "S_2") (pintype "passive"))
      (node (ref "U1") (pin "4") (pinfunction "GND_4") (pintype "power_in"))
      (node (ref "U1") (pin "9") (pinfunction "EP_9") (pintype "passive"))
    )
    (net (code "14") (name "N3V3") (class "Default")
      (node (ref "C68") (pin "2") (pinfunction "2_2") (pintype "passive"))
      (node (ref "C78") (pin "2") (pinfunction "2_2") (pintype "passive"))
      (node (ref "C79") (pin "2") (pinfunction "2_2") (pintype "passive"))
      (node (ref "C81") (pin "2") (pinfunction "2_2") (pintype "passive"))
      (node (ref "IC12") (pin "7") (pinfunction "VSS_7") (pintype "power_in"))
      (node (ref "IC13") (pin "7") (pinfunction "VSS_7") (pintype "power_in"))
      (node (ref "R93") (pin "2") (pinfunction "2_2") (pintype "passive"))
      (node (ref "U1") (pin "1") (pinfunction "OUT_1") (pintype "power_in"))
    )
    (net (code "15") (name "Neg_CH3") (class "Default")
      (node (ref "C10") (pin "2") (pinfunction "2_2") (pintype "passive"))
      (node (ref "L2") (pin "2") (pinfunction "2_2") (pintype "passive"))
    )
    (net (code "16") (name "Net-(C1-Pad2)") (class "Default")
      (node (ref "C1") (pin "2") (pinfunction "2_2") (pintype "passive"))
      (node (ref "C11") (pin "2") (pinfunction "2_2") (pintype "passive"))
      (node (ref "C4") (pin "2") (pinfunction "2_2") (pintype "passive"))
      (node (ref "L1") (pin "1") (pinfunction "1_1") (pintype "passive"))
      (node (ref "L10") (pin "1") (pinfunction "1_1") (pintype "passive"))
      (node (ref "R2") (pin "2") (pinfunction "2_2") (pintype "passive"))
    )
    (net (code "17") (name "Net-(C7-Pad2)") (class "Default")
      (node (ref "C7") (pin "2") (pinfunction "2_2") (pintype "passive"))
      (node (ref "R5") (pin "1") (pinfunction "1_1") (pintype "passive"))
    )
    (net (code "18") (name "Net-(C14-Pad2)") (class "Default")
      (node (ref "C14") (pin "2") (pinfunction "2_2") (pintype "passive"))
      (node (ref "C2") (pin "2") (pinfunction "2_2") (pintype "passive"))
      (node (ref "IC1") (pin "10") (pinfunction "OUT_10") (pintype "power_in"))
      (node (ref "IC1") (pin "11") (pinfunction "OUT_11") (pintype "power_in"))
      (node (ref "IC1") (pin "12") (pinfunction "OUT_12") (pintype "power_in"))
      (node (ref "L2") (pin "1") (pinfunction "1_1") (pintype "passive"))
      (node (ref "R11") (pin "1") (pinfunction "1_1") (pintype "passive"))
      (node (ref "R41") (pin "2") (pinfunction "2_2") (pintype "passive"))
    )
    (net (code "19") (name "Net-(D1-A)") (class "Default")
      (node (ref "C3") (pin "2") (pinfunction "2_2") (pintype "passive"))
      (node (ref "D1") (pin "2") (pinfunction "A_2") (pintype "passive"))
      (node (ref "L1") (pin "3") (pinfunction "3_3") (pintype "passive"))
    )
    (net (code "20") (name "Net-(IC1-ILIM)") (class "Default")
      (node (ref "IC1") (pin "4") (pinfunction "ILIM_4") (pintype "input"))
      (node (ref "R4") (pin "2") (pinfunction "2_2") (pintype "passive"))
    )
    (net (code "21") (name "Net-(IC1-SET)") (class "Default")
      (node (ref "C6") (pin "1") (pinfunction "1_1") (pintype "passive"))
      (node (ref "IC1") (pin "8") (pinfunction "SET_8") (pintype "input"))
      (node (ref "R10") (pin "2") (pinfunction "2_2") (pintype "passive"))
      (node (ref "R53") (pin "2") (pinfunction "2_2") (pintype "passive"))
      (node (ref "R58") (pin "2") (pinfunction "2_2") (pintype "passive"))
      (node (ref "R68") (pin "2") (pinfunction "2_2") (pintype "passive"))
      (node (ref "R7") (pin "2") (pinfunction "2_2") (pintype "passive"))
      (node (ref "R8") (pin "2") (pinfunction "2_2") (pintype "passive"))
      (node (ref "R9") (pin "2") (pinfunction "2_2") (pintype "passive"))
      (node (ref "R95") (pin "2") (pinfunction "2_2") (pintype "passive"))
    )
    (net (code "22") (name "Net-(IC2-FBX)") (class "Default")
      (node (ref "IC2") (pin "6") (pinfunction "FBX_6") (pintype "passive"))
      (node (ref "R3") (pin "2") (pinfunction "2_2") (pintype "passive"))
      (node (ref "T15") (pin "3") (pinfunction "C_3") (pintype "passive"))
    )
    (net (code "23") (name "Net-(IC2-INTVcc)") (class "Default")
      (node (ref "C9") (pin "2") (pinfunction "2_2") (pintype "passive"))
      (node (ref "IC2") (pin "3") (pinfunction "INTVcc_3") (pintype "passive"))
    )
    (net (code "24") (name "Net-(IC2-RT)") (class "Default")
      (node (ref "IC2") (pin "7") (pinfunction "RT_7") (pintype "passive"))
      (node (ref "R12") (pin "2") (pinfunction "2_2") (pintype "passive"))
    )
    (net (code "25") (name "Net-(IC2-SS)") (class "Default")
      (node (ref "C8") (pin "2") (pinfunction "2_2") (pintype "passive"))
      (node (ref "IC2") (pin "8") (pinfunction "SS_8") (pintype "passive"))
    )
    (net (code "26") (name "Net-(IC2-SW)") (class "Default")
      (node (ref "C3") (pin "1") (pinfunction "1_1") (pintype "passive"))
      (node (ref "IC2") (pin "10") (pinfunction "SW_10") (pintype "passive"))
      (node (ref "L1") (pin "4") (pinfunction "4_4") (pintype "passive"))
    )
    (net (code "27") (name "Net-(IC2-VIN)") (class "Default")
      (node (ref "C15") (pin "1") (pinfunction "1_1") (pintype "passive"))
      (node (ref "C16") (pin "2") (pinfunction "2_2") (pintype "passive"))
      (node (ref "C17") (pin "2") (pinfunction "2_2") (pintype "passive"))
      (node (ref "IC2") (pin "2") (pinfunction "VIN_2") (pintype "passive"))
      (node (ref "L1") (pin "2") (pinfunction "2_2") (pintype "passive"))
      (node (ref "L3") (pin "2") (pinfunction "2_2") (pintype "passive"))
      (node (ref "R57") (pin "1") (pinfunction "1_1") (pintype "passive"))
    )
    (net (code "28") (name "Net-(IC2-Vc)") (class "Default")
      (node (ref "IC2") (pin "5") (pinfunction "Vc_5") (pintype "passive"))
      (node (ref "R5") (pin "2") (pinfunction "2_2") (pintype "passive"))
    )
    (net (code "29") (name "Net-(IC10-IN-)") (class "Default")
      (node (ref "C87") (pin "1") (pinfunction "1_1") (pintype "passive"))
      (node (ref "IC10") (pin "3") (pinfunction "IN-_3") (pintype "input"))
      (node (ref "R40") (pin "1") (pinfunction "1_1") (pintype "passive"))
      (node (ref "R42") (pin "2") (pinfunction "2_2") (pintype "passive"))
    )
    (net (code "30") (name "Net-(IC12A-OUT)") (class "Default")
      (node (ref "IC12") (pin "2") (pinfunction "OUT_2") (pintype "output"))
      (node (ref "T10") (pin "1") (pinfunction "G_1") (pintype "passive"))
    )
    (net (code "31") (name "Net-(IC12B-OUT)") (class "Default")
      (node (ref "IC12") (pin "4") (pinfunction "OUT_4") (pintype "output"))
      (node (ref "T11") (pin "1") (pinfunction "G_1") (pintype "passive"))
    )
    (net (code "32") (name "Net-(IC12C-OUT)") (class "Default")
      (node (ref "IC12") (pin "6") (pinfunction "OUT_6") (pintype "output"))
      (node (ref "T20") (pin "1") (pinfunction "G_1") (pintype "passive"))
    )
    (net (code "33") (name "Net-(IC12D-OUT)") (class "Default")
      (node (ref "IC12") (pin "8") (pinfunction "OUT_8") (pintype "output"))
      (node (ref "T12") (pin "1") (pinfunction "G_1") (pintype "passive"))
    )
    (net (code "34") (name "Net-(IC12E-OUT)") (class "Default")
      (node (ref "IC12") (pin "10") (pinfunction "OUT_10") (pintype "output"))
      (node (ref "T18") (pin "1") (pinfunction "G_1") (pintype "passive"))
    )
    (net (code "35") (name "Net-(IC12F-OUT)") (class "Default")
      (node (ref "IC12") (pin "12") (pinfunction "OUT_12") (pintype "output"))
      (node (ref "T13") (pin "1") (pinfunction "G_1") (pintype "passive"))
    )
    (net (code "36") (name "Net-(IC13A-OUT)") (class "Default")
      (node (ref "IC13") (pin "2") (pinfunction "OUT_2") (pintype "output"))
      (node (ref "T14") (pin "1") (pinfunction "G_1") (pintype "passive"))
    )
    (net (code "37") (name "Net-(IC13B-OUT)") (class "Default")
      (node (ref "IC13") (pin "4") (pinfunction "OUT_4") (pintype "output"))
      (node (ref "T19") (pin "1") (pinfunction "G_1") (pintype "passive"))
    )
    (net (code "38") (name "Net-(L10-Pad2)") (class "Default")
      (node (ref "L10") (pin "2") (pinfunction "2_2") (pintype "passive"))
      (node (ref "L16") (pin "1") (pinfunction "1_1") (pintype "passive"))
    )
    (net (code "39") (name "Net-(P1-CCW)") (class "Default")
      (node (ref "P1") (pin "1") (pinfunction "CCW_1") (pintype "passive"))
      (node (ref "P1") (pin "2") (pinfunction "W_2") (pintype "passive"))
      (node (ref "R28") (pin "2") (pinfunction "2_2") (pintype "passive"))
      (node (ref "R95") (pin "1") (pinfunction "1_1") (pintype "passive"))
    )
    (net (code "40") (name "Net-(P1-CW)") (class "Default")
      (node (ref "P1") (pin "3") (pinfunction "CW_3") (pintype "passive"))
      (node (ref "R28") (pin "1") (pinfunction "1_1") (pintype "passive"))
      (node (ref "T20") (pin "3") (pinfunction "D_3") (pintype "passive"))
    )
    (net (code "41") (name "Net-(R6-Pad2)") (class "Default")
      (node (ref "R6") (pin "2") (pinfunction "2_2") (pintype "passive"))
      (node (ref "R68") (pin "1") (pinfunction "1_1") (pintype "passive"))
    )
    (net (code "42") (name "Net-(R41-Pad1)") (class "Default")
      (node (ref "R41") (pin "1") (pinfunction "1_1") (pintype "passive"))
      (node (ref "R42") (pin "1") (pinfunction "1_1") (pintype "passive"))
      (node (ref "R43") (pin "2") (pinfunction "2_2") (pintype "passive"))
    )
    (net (code "43") (name "Net-(R111-Pad1)") (class "Default")
      (node (ref "R111") (pin "1") (pinfunction "1_1") (pintype "passive"))
      (node (ref "R57") (pin "2") (pinfunction "2_2") (pintype "passive"))
    )
    (net (code "44") (name "Net-(R115-Pad2)") (class "Default")
      (node (ref "R115") (pin "2") (pinfunction "2_2") (pintype "passive"))
      (node (ref "R2") (pin "1") (pinfunction "1_1") (pintype "passive"))
    )
    (net (code "45") (name "Net-(T10-D)") (class "Default")
      (node (ref "R6") (pin "1") (pinfunction "1_1") (pintype "passive"))
      (node (ref "T10") (pin "3") (pinfunction "D_3") (pintype "passive"))
    )
    (net (code "46") (name "Net-(T11-D)") (class "Default")
      (node (ref "R7") (pin "1") (pinfunction "1_1") (pintype "passive"))
      (node (ref "T11") (pin "3") (pinfunction "D_3") (pintype "passive"))
    )
    (net (code "47") (name "Net-(T12-D)") (class "Default")
      (node (ref "R8") (pin "1") (pinfunction "1_1") (pintype "passive"))
      (node (ref "T12") (pin "3") (pinfunction "D_3") (pintype "passive"))
    )
    (net (code "48") (name "Net-(T13-D)") (class "Default")
      (node (ref "R9") (pin "1") (pinfunction "1_1") (pintype "passive"))
      (node (ref "T13") (pin "3") (pinfunction "D_3") (pintype "passive"))
    )
    (net (code "49") (name "Net-(T14-D)") (class "Default")
      (node (ref "R10") (pin "1") (pinfunction "1_1") (pintype "passive"))
      (node (ref "T14") (pin "3") (pinfunction "D_3") (pintype "passive"))
    )
    (net (code "50") (name "Net-(T15-B)") (class "Default")
      (node (ref "R11") (pin "2") (pinfunction "2_2") (pintype "passive"))
      (node (ref "T15") (pin "1") (pinfunction "B_1") (pintype "passive"))
    )
    (net (code "51") (name "Net-(T15-E)") (class "Default")
      (node (ref "C4") (pin "1") (pinfunction "1_1") (pintype "passive"))
      (node (ref "R115") (pin "1") (pinfunction "1_1") (pintype "passive"))
      (node (ref "T15") (pin "2") (pinfunction "E_2") (pintype "passive"))
    )
    (net (code "52") (name "Net-(T18-D)") (class "Default")
      (node (ref "R53") (pin "1") (pinfunction "1_1") (pintype "passive"))
      (node (ref "T18") (pin "3") (pinfunction "D_3") (pintype "passive"))
    )
    (net (code "53") (name "Net-(T19-D)") (class "Default")
      (node (ref "R58") (pin "1") (pinfunction "1_1") (pintype "passive"))
      (node (ref "T19") (pin "3") (pinfunction "D_3") (pintype "passive"))
    )
    (net (code "54") (name "Net-(U1-FB)") (class "Default")
      (node (ref "C81") (pin "1") (pinfunction "1_1") (pintype "passive"))
      (node (ref "R93") (pin "1") (pinfunction "1_1") (pintype "passive"))
      (node (ref "R94") (pin "2") (pinfunction "2_2") (pintype "passive"))
      (node (ref "U1") (pin "2") (pinfunction "FB_2") (pintype "input"))
    )
    (net (code "55") (name "Net-(U1-NR{slash}SS)") (class "Default")
      (node (ref "C89") (pin "2") (pinfunction "2_2") (pintype "passive"))
      (node (ref "U1") (pin "6") (pinfunction "NR/SS_6") (pintype "passive"))
    )
    (net (code "56") (name "P3V3i") (class "Default")
      (node (ref "C65") (pin "2") (pinfunction "2_2") (pintype "passive"))
      (node (ref "C86") (pin "2") (pinfunction "2_2") (pintype "passive"))
      (node (ref "IC10") (pin "5") (pinfunction "V+_5") (pintype "power_in"))
    )
    (net (code "57") (name "P12V0") (class "Default")
      (node (ref "C5") (pin "2") (pinfunction "2_2") (pintype "passive"))
      (node (ref "C64") (pin "2") (pinfunction "2_2") (pintype "passive"))
      (node (ref "IC1") (pin "6") (pinfunction "IMONN_6") (pintype "input"))
      (node (ref "L3") (pin "1") (pinfunction "1_1") (pintype "passive"))
    )
    (net (code "58") (name "Vee") (class "Default")
      (node (ref "C12") (pin "2") (pinfunction "2_2") (pintype "passive"))
      (node (ref "C13") (pin "2") (pinfunction "2_2") (pintype "passive"))
      (node (ref "C63") (pin "2") (pinfunction "2_2") (pintype "passive"))
      (node (ref "C80") (pin "2") (pinfunction "2_2") (pintype "passive"))
      (node (ref "IC1") (pin "1") (pinfunction "IN_1") (pintype "input"))
      (node (ref "IC1") (pin "13") (pinfunction "EP_13") (pintype "power_in"))
      (node (ref "IC1") (pin "2") (pinfunction "IN_2") (pintype "input"))
      (node (ref "IC1") (pin "3") (pinfunction "IN_3") (pintype "input"))
      (node (ref "IC1") (pin "7") (pinfunction "~{SHDN}_7") (pintype "input"))
      (node (ref "L16") (pin "2") (pinfunction "2_2") (pintype "passive"))
      (node (ref "R4") (pin "1") (pinfunction "1_1") (pintype "passive"))
      (node (ref "U1") (pin "5") (pinfunction "EN_5") (pintype "input"))
      (node (ref "U1") (pin "8") (pinfunction "IN_8") (pintype "power_in"))
    )
    (net (code "59") (name "unconnected-(U1-DNC-Pad7)") (class "Default")
      (node (ref "U1") (pin "7") (pinfunction "DNC_7") (pintype "passive+no_connect"))
    )
    (net (code "60") (name "unconnected-(U1-NC-Pad3)") (class "Default")
      (node (ref "U1") (pin "3") (pinfunction "NC_3") (pintype "passive+no_connect"))
    )
  )
)
